# Raincenter_APP-TS_ARM_ISO_0_02.net
KiCad netlist of a schematic drawn in EAGLE
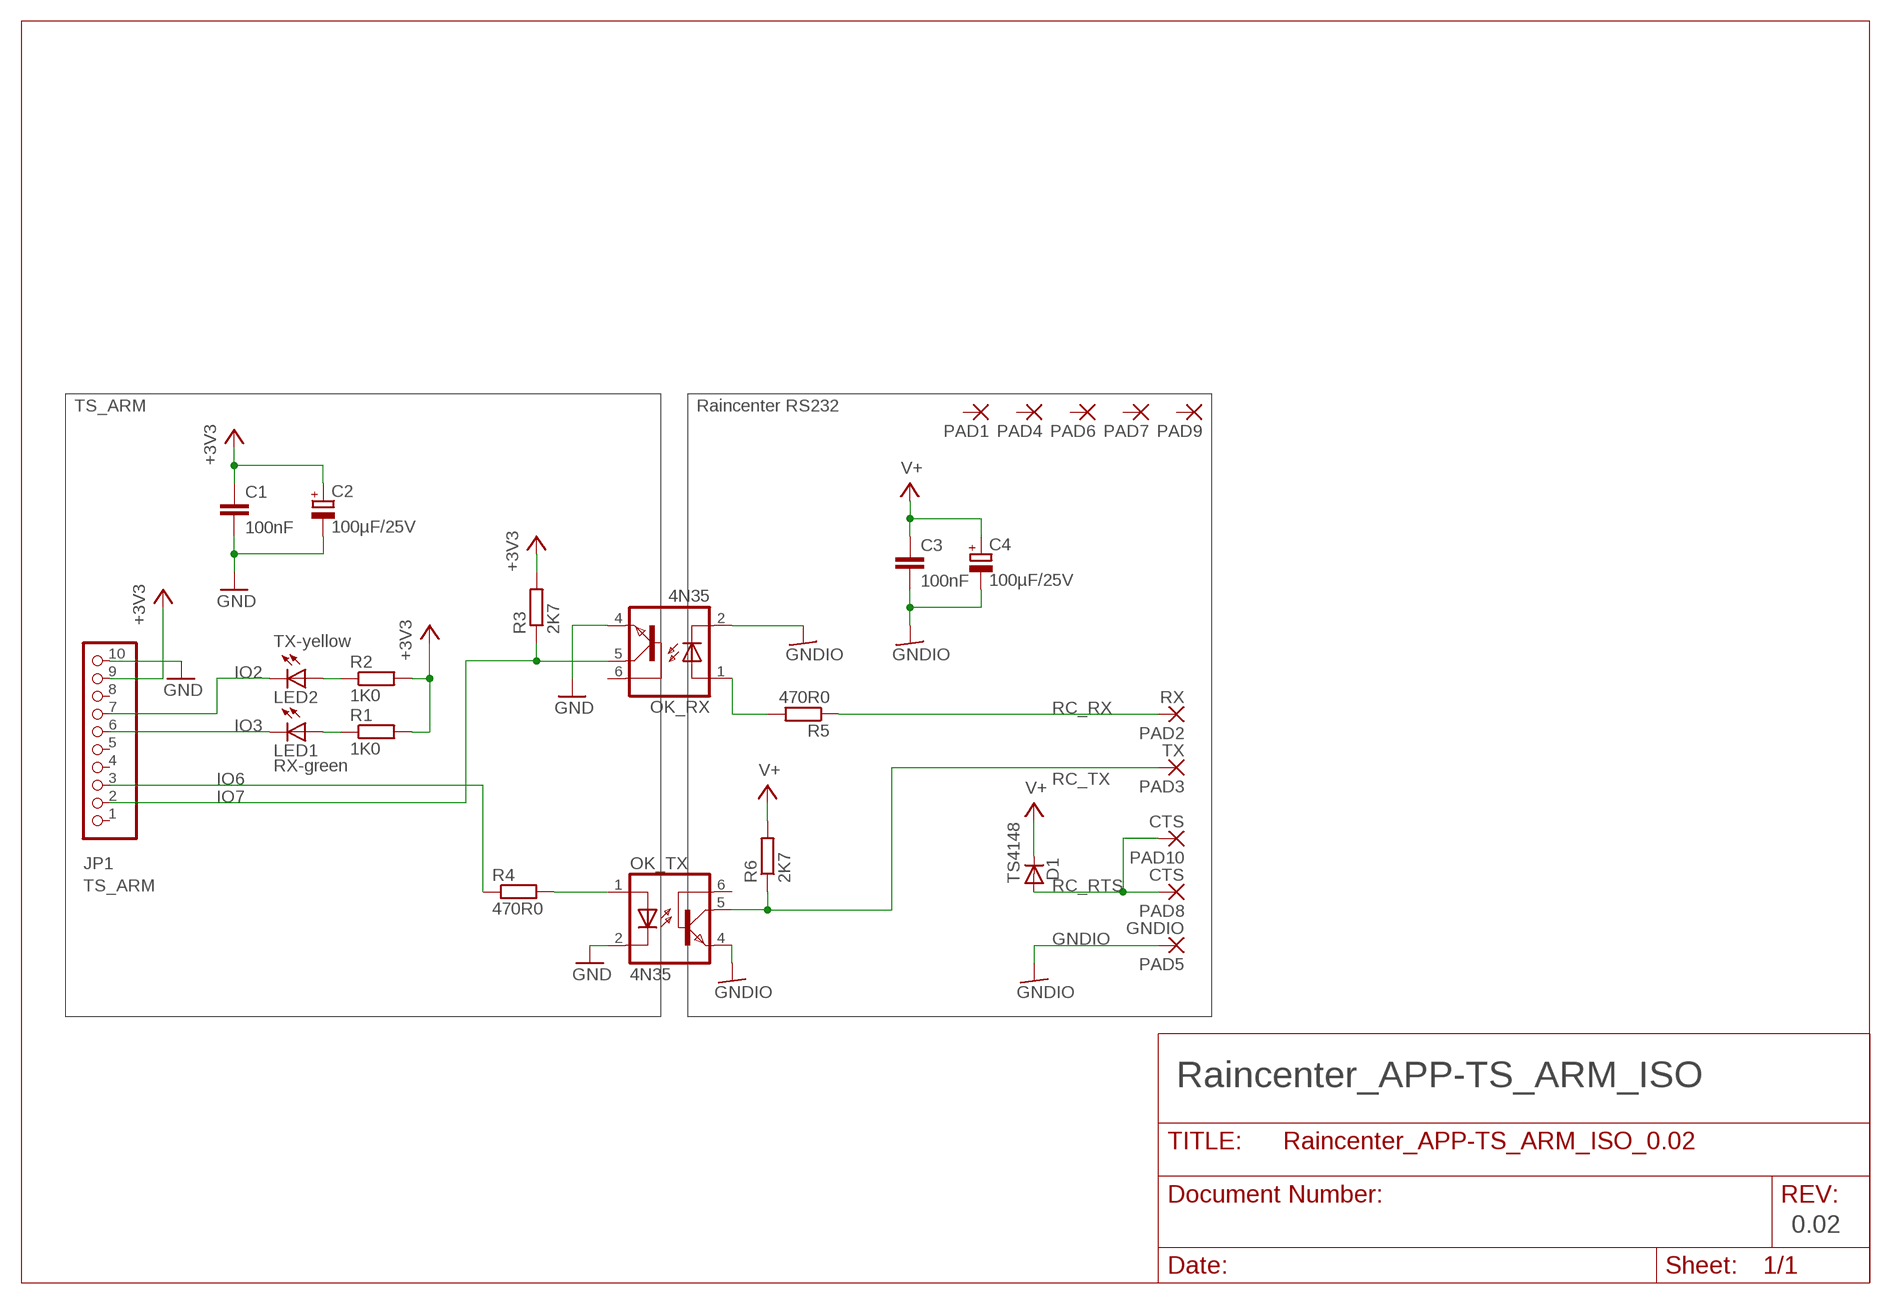
[diagram p0: schematic, sheet 1]

(export (version "E")
  (design (tool "Eeschema 10.0.6"))
  (components
    (comp (ref "C1")
      (value "100nF")
      (footprint "eagle-import:C1206K")
      (libsource (lib "eagle-import") (part "C-EUC1206K"))
    )
    (comp (ref "C2")
      (value "100µF/25V")
      (footprint "eagle-import:PANASONIC_D")
      (libsource (lib "eagle-import") (part "CPOL-EUD"))
    )
    (comp (ref "C3")
      (value "100nF")
      (footprint "eagle-import:C1206K")
      (libsource (lib "eagle-import") (part "C-EUC1206K"))
    )
    (comp (ref "C4")
      (value "100µF/25V")
      (footprint "eagle-import:PANASONIC_D")
      (libsource (lib "eagle-import") (part "CPOL-EUD"))
    )
    (comp (ref "D1")
      (value "TS4148")
      (footprint "eagle-import:1206")
      (libsource (lib "eagle-import") (part "TS4148"))
    )
    (comp (ref "JP1")
      (value "TS_ARM")
      (footprint "eagle-import:1X10")
      (libsource (lib "eagle-import") (part "PINHD-1X10"))
    )
    (comp (ref "LED1")
      (value "RX-green")
      (footprint "eagle-import:CHIPLED_1206")
      (libsource (lib "eagle-import") (part "LEDCHIPLED_1206"))
    )
    (comp (ref "LED2")
      (value "TX-yellow")
      (footprint "eagle-import:CHIPLED_1206")
      (libsource (lib "eagle-import") (part "LEDCHIPLED_1206"))
    )
    (comp (ref "OK_RX")
      (value "4N35")
      (footprint "eagle-import:DIL06")
      (fields (field (name "MF") "FAIRCHILD SEMICONDUCTOR"))
      (libsource (lib "eagle-import") (part "4N35"))
    )
    (comp (ref "OK_TX")
      (value "4N35")
      (footprint "eagle-import:DIL06")
      (fields (field (name "MF") "FAIRCHILD SEMICONDUCTOR"))
      (libsource (lib "eagle-import") (part "4N35"))
    )
    (comp (ref "PAD1")
      (value "WIREPADSMD1,27-254")
      (footprint "eagle-import:SMD1,27-2,54")
      (libsource (lib "eagle-import") (part "WIREPADSMD1,27-254"))
    )
    (comp (ref "PAD2")
      (value "RX")
      (footprint "eagle-import:SMD1,27-2,54")
      (libsource (lib "eagle-import") (part "WIREPADSMD1,27-254"))
    )
    (comp (ref "PAD3")
      (value "TX")
      (footprint "eagle-import:SMD1,27-2,54")
      (libsource (lib "eagle-import") (part "WIREPADSMD1,27-254"))
    )
    (comp (ref "PAD4")
      (value "WIREPADSMD1,27-254")
      (footprint "eagle-import:SMD1,27-2,54")
      (libsource (lib "eagle-import") (part "WIREPADSMD1,27-254"))
    )
    (comp (ref "PAD5")
      (value "GNDIO")
      (footprint "eagle-import:SMD1,27-2,54")
      (libsource (lib "eagle-import") (part "WIREPADSMD1,27-254"))
    )
    (comp (ref "PAD6")
      (value "WIREPADSMD1,27-254")
      (footprint "eagle-import:SMD1,27-2,54")
      (libsource (lib "eagle-import") (part "WIREPADSMD1,27-254"))
    )
    (comp (ref "PAD7")
      (value "WIREPADSMD1,27-254")
      (footprint "eagle-import:SMD1,27-2,54")
      (libsource (lib "eagle-import") (part "WIREPADSMD1,27-254"))
    )
    (comp (ref "PAD8")
      (value "CTS")
      (footprint "eagle-import:SMD1,27-2,54")
      (libsource (lib "eagle-import") (part "WIREPADSMD1,27-254"))
    )
    (comp (ref "PAD9")
      (value "WIREPADSMD1,27-254")
      (footprint "eagle-import:SMD1,27-2,54")
      (libsource (lib "eagle-import") (part "WIREPADSMD1,27-254"))
    )
    (comp (ref "PAD10")
      (value "CTS")
      (footprint "eagle-import:SMD1,27-2,54")
      (libsource (lib "eagle-import") (part "WIREPADSMD1,27-254"))
    )
    (comp (ref "R1")
      (value "1K0")
      (footprint "eagle-import:R1206")
      (libsource (lib "eagle-import") (part "R-EU_R1206"))
    )
    (comp (ref "R2")
      (value "1K0")
      (footprint "eagle-import:R1206")
      (libsource (lib "eagle-import") (part "R-EU_R1206"))
    )
    (comp (ref "R3")
      (value "2K7")
      (footprint "eagle-import:R1206")
      (libsource (lib "eagle-import") (part "R-EU_R1206"))
    )
    (comp (ref "R4")
      (value "470R0")
      (footprint "eagle-import:R1206")
      (libsource (lib "eagle-import") (part "R-EU_R1206"))
    )
    (comp (ref "R5")
      (value "470R0")
      (footprint "eagle-import:R1206")
      (libsource (lib "eagle-import") (part "R-EU_R1206"))
    )
    (comp (ref "R6")
      (value "2K7")
      (footprint "eagle-import:R1206")
      (libsource (lib "eagle-import") (part "R-EU_R1206"))
    )
  )
  (nets
    (net (code "1") (name "+3V3") (class "Default")
      (node (ref "C1") (pin "1") (pinfunction "1_1") (pintype "passive"))
      (node (ref "C2") (pin "+") (pinfunction "+_+") (pintype "passive"))
      (node (ref "JP1") (pin "9") (pinfunction "9_9") (pintype "passive"))
      (node (ref "R1") (pin "2") (pinfunction "2_2") (pintype "passive"))
      (node (ref "R2") (pin "2") (pinfunction "2_2") (pintype "passive"))
      (node (ref "R3") (pin "2") (pinfunction "2_2") (pintype "passive"))
    )
    (net (code "2") (name "/IO2") (class "Default")
      (node (ref "JP1") (pin "7") (pinfunction "7_7") (pintype "passive"))
      (node (ref "LED2") (pin "C") (pinfunction "C_C") (pintype "passive"))
    )
    (net (code "3") (name "/IO3") (class "Default")
      (node (ref "JP1") (pin "6") (pinfunction "6_6") (pintype "passive"))
      (node (ref "LED1") (pin "C") (pinfunction "C_C") (pintype "passive"))
    )
    (net (code "4") (name "/IO6") (class "Default")
      (node (ref "JP1") (pin "3") (pinfunction "3_3") (pintype "passive"))
      (node (ref "R4") (pin "1") (pinfunction "1_1") (pintype "passive"))
    )
    (net (code "5") (name "/IO7") (class "Default")
      (node (ref "JP1") (pin "2") (pinfunction "2_2") (pintype "passive"))
      (node (ref "OK_RX") (pin "5") (pinfunction "COL_5") (pintype "passive"))
      (node (ref "R3") (pin "1") (pinfunction "1_1") (pintype "passive"))
    )
    (net (code "6") (name "/RC_RTS") (class "Default")
      (node (ref "D1") (pin "ANODE") (pinfunction "A_ANODE") (pintype "passive"))
      (node (ref "PAD10") (pin "1") (pinfunction "P_1") (pintype "passive"))
      (node (ref "PAD8") (pin "1") (pinfunction "P_1") (pintype "passive"))
    )
    (net (code "7") (name "/RC_RX") (class "Default")
      (node (ref "PAD2") (pin "1") (pinfunction "P_1") (pintype "passive"))
      (node (ref "R5") (pin "1") (pinfunction "1_1") (pintype "passive"))
    )
    (net (code "8") (name "/RC_TX") (class "Default")
      (node (ref "OK_TX") (pin "5") (pinfunction "COL_5") (pintype "passive"))
      (node (ref "PAD3") (pin "1") (pinfunction "P_1") (pintype "passive"))
      (node (ref "R6") (pin "1") (pinfunction "1_1") (pintype "passive"))
    )
    (net (code "9") (name "GND") (class "Default")
      (node (ref "C1") (pin "2") (pinfunction "2_2") (pintype "passive"))
      (node (ref "C2") (pin "-") (pinfunction "-_-") (pintype "passive"))
      (node (ref "JP1") (pin "10") (pinfunction "10_10") (pintype "passive"))
      (node (ref "OK_RX") (pin "4") (pinfunction "EMI_4") (pintype "passive"))
      (node (ref "OK_TX") (pin "2") (pinfunction "C_2") (pintype "passive"))
    )
    (net (code "10") (name "GNDIO") (class "Default")
      (node (ref "C3") (pin "2") (pinfunction "2_2") (pintype "passive"))
      (node (ref "C4") (pin "-") (pinfunction "-_-") (pintype "passive"))
      (node (ref "OK_RX") (pin "2") (pinfunction "C_2") (pintype "passive"))
      (node (ref "OK_TX") (pin "4") (pinfunction "EMI_4") (pintype "passive"))
      (node (ref "PAD5") (pin "1") (pinfunction "P_1") (pintype "passive"))
    )
    (net (code "11") (name "Net-(LED1-PadA)") (class "Default")
      (node (ref "LED1") (pin "A") (pinfunction "A_A") (pintype "passive"))
      (node (ref "R1") (pin "1") (pinfunction "1_1") (pintype "passive"))
    )
    (net (code "12") (name "Net-(LED2-PadA)") (class "Default")
      (node (ref "LED2") (pin "A") (pinfunction "A_A") (pintype "passive"))
      (node (ref "R2") (pin "1") (pinfunction "1_1") (pintype "passive"))
    )
    (net (code "13") (name "Net-(OK_RX-A)") (class "Default")
      (node (ref "OK_RX") (pin "1") (pinfunction "A_1") (pintype "passive"))
      (node (ref "R5") (pin "2") (pinfunction "2_2") (pintype "passive"))
    )
    (net (code "14") (name "Net-(OK_TX-A)") (class "Default")
      (node (ref "OK_TX") (pin "1") (pinfunction "A_1") (pintype "passive"))
      (node (ref "R4") (pin "2") (pinfunction "2_2") (pintype "passive"))
    )
    (net (code "15") (name "V+") (class "Default")
      (node (ref "C3") (pin "1") (pinfunction "1_1") (pintype "passive"))
      (node (ref "C4") (pin "+") (pinfunction "+_+") (pintype "passive"))
      (node (ref "D1") (pin "KATHODE") (pinfunction "K_KATHODE") (pintype "passive"))
      (node (ref "R6") (pin "2") (pinfunction "2_2") (pintype "passive"))
    )
    (net (code "16") (name "unconnected-(JP1-Pad1)") (class "Default")
      (node (ref "JP1") (pin "1") (pinfunction "1_1") (pintype "passive"))
    )
    (net (code "17") (name "unconnected-(JP1-Pad4)") (class "Default")
      (node (ref "JP1") (pin "4") (pinfunction "4_4") (pintype "passive"))
    )
    (net (code "18") (name "unconnected-(JP1-Pad5)") (class "Default")
      (node (ref "JP1") (pin "5") (pinfunction "5_5") (pintype "passive"))
    )
    (net (code "19") (name "unconnected-(JP1-Pad8)") (class "Default")
      (node (ref "JP1") (pin "8") (pinfunction "8_8") (pintype "passive"))
    )
    (net (code "20") (name "unconnected-(OK_RX-BAS-Pad6)") (class "Default")
      (node (ref "OK_RX") (pin "6") (pinfunction "BAS_6") (pintype "passive"))
    )
    (net (code "21") (name "unconnected-(OK_TX-BAS-Pad6)") (class "Default")
      (node (ref "OK_TX") (pin "6") (pinfunction "BAS_6") (pintype "passive"))
    )
    (net (code "22") (name "unconnected-(PAD1-P-Pad1)") (class "Default")
      (node (ref "PAD1") (pin "1") (pinfunction "P_1") (pintype "passive"))
    )
    (net (code "23") (name "unconnected-(PAD4-P-Pad1)") (class "Default")
      (node (ref "PAD4") (pin "1") (pinfunction "P_1") (pintype "passive"))
    )
    (net (code "24") (name "unconnected-(PAD6-P-Pad1)") (class "Default")
      (node (ref "PAD6") (pin "1") (pinfunction "P_1") (pintype "passive"))
    )
    (net (code "25") (name "unconnected-(PAD7-P-Pad1)") (class "Default")
      (node (ref "PAD7") (pin "1") (pinfunction "P_1") (pintype "passive"))
    )
    (net (code "26") (name "unconnected-(PAD9-P-Pad1)") (class "Default")
      (node (ref "PAD9") (pin "1") (pinfunction "P_1") (pintype "passive"))
    )
  )
)
